# board.net
KiCad netlist of a schematic drawn in EAGLE
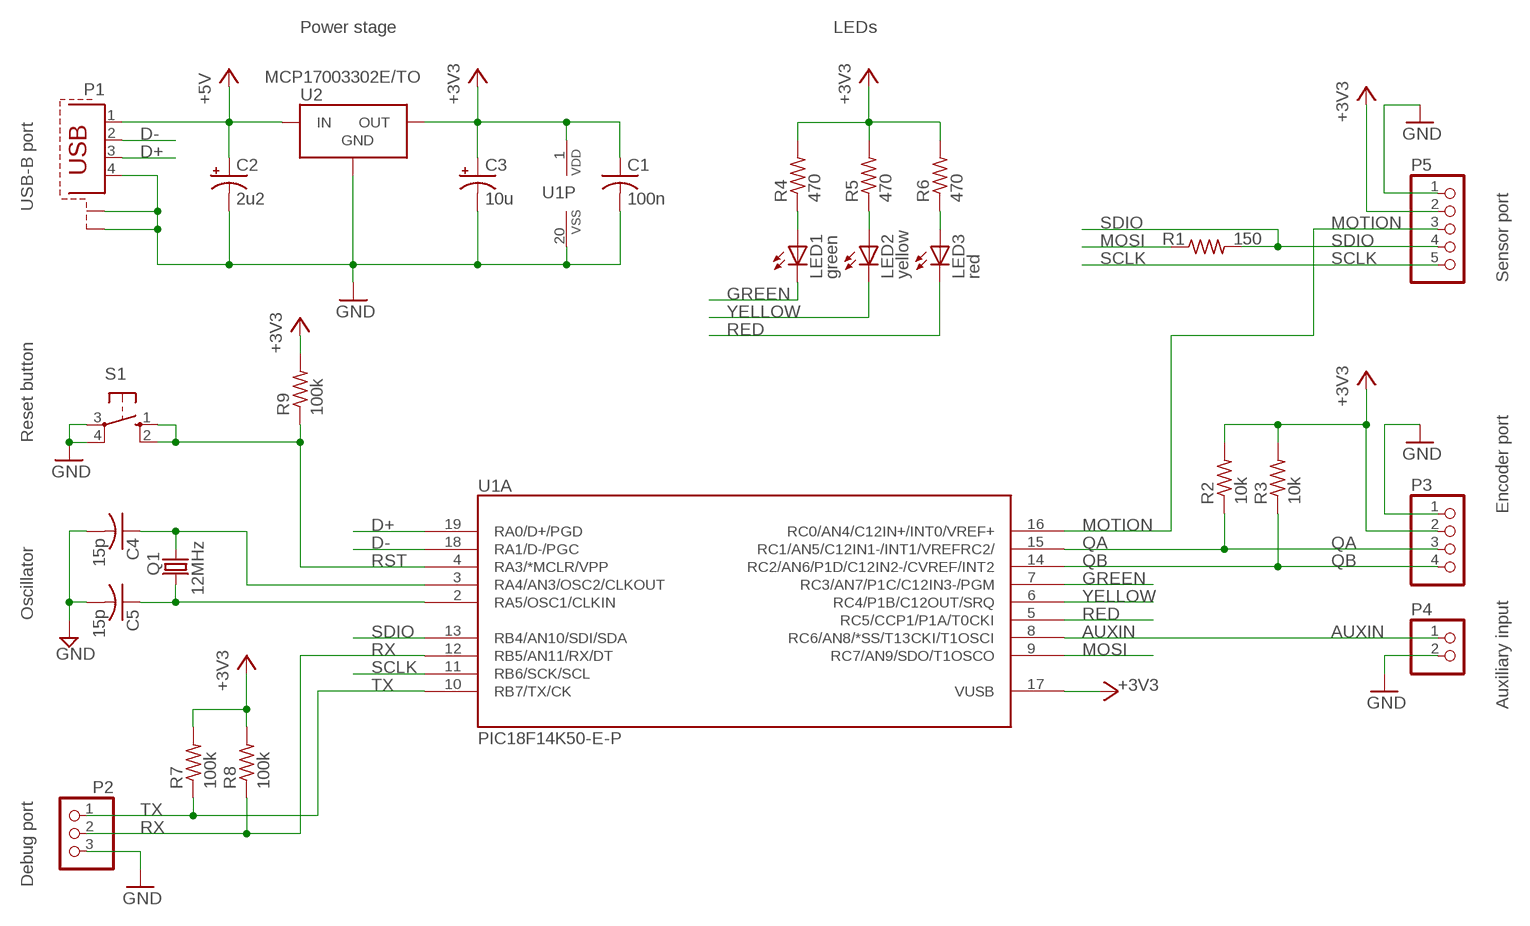
[diagram p0: schematic, sheet 1]

(export (version "E")
  (design (tool "Eeschema 10.0.6"))
  (components
    (comp (ref "C1")
      (value "100n")
      (footprint "eagle-import:C025-025X050")
      (libsource (lib "eagle-import") (part "C-US025-025X050"))
    )
    (comp (ref "C2")
      (value "2u2")
      (footprint "eagle-import:E2-5")
      (libsource (lib "eagle-import") (part "CPOL-USE2-5"))
    )
    (comp (ref "C3")
      (value "10u")
      (footprint "eagle-import:E2-5")
      (libsource (lib "eagle-import") (part "CPOL-USE2-5"))
    )
    (comp (ref "C4")
      (value "15p")
      (footprint "eagle-import:C025-025X050")
      (libsource (lib "eagle-import") (part "C-US025-025X050"))
    )
    (comp (ref "C5")
      (value "15p")
      (footprint "eagle-import:C025-025X050")
      (libsource (lib "eagle-import") (part "C-US025-025X050"))
    )
    (comp (ref "LED1")
      (value "green")
      (footprint "eagle-import:LED3MM")
      (libsource (lib "eagle-import") (part "LED3MM"))
    )
    (comp (ref "LED2")
      (value "yellow")
      (footprint "eagle-import:LED3MM")
      (libsource (lib "eagle-import") (part "LED3MM"))
    )
    (comp (ref "LED3")
      (value "red")
      (footprint "eagle-import:LED3MM")
      (libsource (lib "eagle-import") (part "LED3MM"))
    )
    (comp (ref "P1")
      (value "PN61729-S")
      (footprint "eagle-import:PN61729-S")
      (libsource (lib "eagle-import") (part "PN61729-S"))
    )
    (comp (ref "P2")
      (value "PINHD-1X3")
      (footprint "eagle-import:1X03")
      (libsource (lib "eagle-import") (part "PINHD-1X3"))
    )
    (comp (ref "P3")
      (value "PINHD-1X4")
      (footprint "eagle-import:1X04")
      (libsource (lib "eagle-import") (part "PINHD-1X4"))
    )
    (comp (ref "P4")
      (value "PINHD-1X2")
      (footprint "eagle-import:1X02")
      (libsource (lib "eagle-import") (part "PINHD-1X2"))
    )
    (comp (ref "P5")
      (value "PINHD-1X5")
      (footprint "eagle-import:1X05")
      (libsource (lib "eagle-import") (part "PINHD-1X5"))
    )
    (comp (ref "Q1")
      (value "12MHz")
      (footprint "eagle-import:HC49_S")
      (libsource (lib "eagle-import") (part "CRYSTALHC49S"))
    )
    (comp (ref "R1")
      (value "150")
      (footprint "eagle-import:0207_10")
      (libsource (lib "eagle-import") (part "R-US_0207/10"))
    )
    (comp (ref "R2")
      (value "10k")
      (footprint "eagle-import:0204_5")
      (libsource (lib "eagle-import") (part "R-US_0204/5"))
    )
    (comp (ref "R3")
      (value "10k")
      (footprint "eagle-import:0204_5")
      (libsource (lib "eagle-import") (part "R-US_0204/5"))
    )
    (comp (ref "R4")
      (value "470")
      (footprint "eagle-import:0204_5")
      (libsource (lib "eagle-import") (part "R-US_0204/5"))
    )
    (comp (ref "R5")
      (value "470")
      (footprint "eagle-import:0204_5")
      (libsource (lib "eagle-import") (part "R-US_0204/5"))
    )
    (comp (ref "R6")
      (value "470")
      (footprint "eagle-import:0204_5")
      (libsource (lib "eagle-import") (part "R-US_0204/5"))
    )
    (comp (ref "R7")
      (value "100k")
      (footprint "eagle-import:0204_5")
      (libsource (lib "eagle-import") (part "R-US_0204/5"))
    )
    (comp (ref "R8")
      (value "100k")
      (footprint "eagle-import:0204_5")
      (libsource (lib "eagle-import") (part "R-US_0204/5"))
    )
    (comp (ref "R9")
      (value "100k")
      (footprint "eagle-import:0204_5")
      (libsource (lib "eagle-import") (part "R-US_0204/5"))
    )
    (comp (ref "S1")
      (value "10-XX")
      (footprint "eagle-import:B3F-10XX")
      (fields (field (name "MPN") "B3F-1000"))
      (libsource (lib "eagle-import") (part "10-XX"))
    )
    (comp (ref "U1")
      (value "PIC18F14K50-E-P")
      (footprint "eagle-import:DIL20")
      (libsource (lib "eagle-import") (part "PIC18F14K50-E-P"))
    )
    (comp (ref "U2")
      (value "MCP17003302E/TO")
      (footprint "eagle-import:TO-92")
      (libsource (lib "eagle-import") (part "MCP17003302E/TO"))
    )
  )
  (nets
    (net (code "1") (name "+3V3") (class "Default")
      (node (ref "C1") (pin "1") (pinfunction "1_1") (pintype "passive"))
      (node (ref "C3") (pin "+") (pinfunction "+_+") (pintype "passive"))
      (node (ref "P3") (pin "2") (pinfunction "2_2") (pintype "passive"))
      (node (ref "P5") (pin "2") (pinfunction "2_2") (pintype "passive"))
      (node (ref "R2") (pin "2") (pinfunction "2_2") (pintype "passive"))
      (node (ref "R3") (pin "2") (pinfunction "2_2") (pintype "passive"))
      (node (ref "R4") (pin "2") (pinfunction "2_2") (pintype "passive"))
      (node (ref "R5") (pin "2") (pinfunction "2_2") (pintype "passive"))
      (node (ref "R6") (pin "2") (pinfunction "2_2") (pintype "passive"))
      (node (ref "R7") (pin "2") (pinfunction "2_2") (pintype "passive"))
      (node (ref "R8") (pin "2") (pinfunction "2_2") (pintype "passive"))
      (node (ref "R9") (pin "2") (pinfunction "2_2") (pintype "passive"))
      (node (ref "U1") (pin "1") (pinfunction "VDD_1") (pintype "passive"))
      (node (ref "U1") (pin "17") (pinfunction "VUSB_17") (pintype "passive"))
      (node (ref "U2") (pin "OUT") (pinfunction "OUT_OUT") (pintype "passive"))
    )
    (net (code "2") (name "+5V") (class "Default")
      (node (ref "C2") (pin "+") (pinfunction "+_+") (pintype "passive"))
      (node (ref "P1") (pin "1") (pinfunction "1_1") (pintype "passive"))
      (node (ref "U2") (pin "IN") (pinfunction "IN_IN") (pintype "passive"))
    )
    (net (code "3") (name "/AUXIN") (class "Default")
      (node (ref "P4") (pin "1") (pinfunction "1_1") (pintype "passive"))
      (node (ref "U1") (pin "8") (pinfunction "RC6/AN8/*SS/T13CKI/T1OSCI_8") (pintype "bidirectional"))
    )
    (net (code "4") (name "/D+") (class "Default")
      (node (ref "P1") (pin "3") (pinfunction "3_3") (pintype "passive"))
      (node (ref "U1") (pin "19") (pinfunction "RA0/D+/PGD_19") (pintype "bidirectional"))
    )
    (net (code "5") (name "/D-") (class "Default")
      (node (ref "P1") (pin "2") (pinfunction "2_2") (pintype "passive"))
      (node (ref "U1") (pin "18") (pinfunction "RA1/D-/PGC_18") (pintype "bidirectional"))
    )
    (net (code "6") (name "/GREEN") (class "Default")
      (node (ref "LED1") (pin "K") (pinfunction "C_K") (pintype "passive"))
      (node (ref "U1") (pin "7") (pinfunction "RC3/AN7/P1C/C12IN3-/PGM_7") (pintype "bidirectional"))
    )
    (net (code "7") (name "/MOSI") (class "Default")
      (node (ref "R1") (pin "1") (pinfunction "1_1") (pintype "passive"))
      (node (ref "U1") (pin "9") (pinfunction "RC7/AN9/SDO/T1OSCO_9") (pintype "bidirectional"))
    )
    (net (code "8") (name "/MOTION") (class "Default")
      (node (ref "P5") (pin "3") (pinfunction "3_3") (pintype "passive"))
      (node (ref "U1") (pin "16") (pinfunction "RC0/AN4/C12IN+/INT0/VREF+_16") (pintype "bidirectional"))
    )
    (net (code "9") (name "/QA") (class "Default")
      (node (ref "P3") (pin "3") (pinfunction "3_3") (pintype "passive"))
      (node (ref "R2") (pin "1") (pinfunction "1_1") (pintype "passive"))
      (node (ref "U1") (pin "15") (pinfunction "RC1/AN5/C12IN1-/INT1/VREFRC2/_15") (pintype "bidirectional"))
    )
    (net (code "10") (name "/QB") (class "Default")
      (node (ref "P3") (pin "4") (pinfunction "4_4") (pintype "passive"))
      (node (ref "R3") (pin "1") (pinfunction "1_1") (pintype "passive"))
      (node (ref "U1") (pin "14") (pinfunction "RC2/AN6/P1D/C12IN2-/CVREF/INT2_14") (pintype "bidirectional"))
    )
    (net (code "11") (name "/RED") (class "Default")
      (node (ref "LED3") (pin "K") (pinfunction "C_K") (pintype "passive"))
      (node (ref "U1") (pin "5") (pinfunction "RC5/CCP1/P1A/T0CKI_5") (pintype "bidirectional"))
    )
    (net (code "12") (name "/RST") (class "Default")
      (node (ref "R9") (pin "1") (pinfunction "1_1") (pintype "passive"))
      (node (ref "S1") (pin "1") (pinfunction "S_1") (pintype "passive"))
      (node (ref "S1") (pin "2") (pinfunction "S1_2") (pintype "passive"))
      (node (ref "U1") (pin "4") (pinfunction "RA3/*MCLR/VPP_4") (pintype "input"))
    )
    (net (code "13") (name "/RX") (class "Default")
      (node (ref "P2") (pin "2") (pinfunction "2_2") (pintype "passive"))
      (node (ref "R8") (pin "1") (pinfunction "1_1") (pintype "passive"))
      (node (ref "U1") (pin "12") (pinfunction "RB5/AN11/RX/DT_12") (pintype "bidirectional"))
    )
    (net (code "14") (name "/SCLK") (class "Default")
      (node (ref "P5") (pin "5") (pinfunction "5_5") (pintype "passive"))
      (node (ref "U1") (pin "11") (pinfunction "RB6/SCK/SCL_11") (pintype "bidirectional"))
    )
    (net (code "15") (name "/SDIO") (class "Default")
      (node (ref "P5") (pin "4") (pinfunction "4_4") (pintype "passive"))
      (node (ref "R1") (pin "2") (pinfunction "2_2") (pintype "passive"))
      (node (ref "U1") (pin "13") (pinfunction "RB4/AN10/SDI/SDA_13") (pintype "bidirectional"))
    )
    (net (code "16") (name "/TX") (class "Default")
      (node (ref "P2") (pin "1") (pinfunction "1_1") (pintype "passive"))
      (node (ref "R7") (pin "1") (pinfunction "1_1") (pintype "passive"))
      (node (ref "U1") (pin "10") (pinfunction "RB7/TX/CK_10") (pintype "bidirectional"))
    )
    (net (code "17") (name "/YELLOW") (class "Default")
      (node (ref "LED2") (pin "K") (pinfunction "C_K") (pintype "passive"))
      (node (ref "U1") (pin "6") (pinfunction "RC4/P1B/C12OUT/SRQ_6") (pintype "bidirectional"))
    )
    (net (code "18") (name "GND") (class "Default")
      (node (ref "C1") (pin "2") (pinfunction "2_2") (pintype "passive"))
      (node (ref "C2") (pin "-") (pinfunction "-_-") (pintype "passive"))
      (node (ref "C3") (pin "-") (pinfunction "-_-") (pintype "passive"))
      (node (ref "C4") (pin "2") (pinfunction "2_2") (pintype "passive"))
      (node (ref "C5") (pin "2") (pinfunction "2_2") (pintype "passive"))
      (node (ref "P1") (pin "4") (pinfunction "4_4") (pintype "passive"))
      (node (ref "P1") (pin "S1") (pinfunction "S1_S1") (pintype "passive"))
      (node (ref "P1") (pin "S2") (pinfunction "S2_S2") (pintype "passive"))
      (node (ref "P2") (pin "3") (pinfunction "3_3") (pintype "passive"))
      (node (ref "P3") (pin "1") (pinfunction "1_1") (pintype "passive"))
      (node (ref "P4") (pin "2") (pinfunction "2_2") (pintype "passive"))
      (node (ref "P5") (pin "1") (pinfunction "1_1") (pintype "passive"))
      (node (ref "S1") (pin "3") (pinfunction "P_3") (pintype "passive"))
      (node (ref "S1") (pin "4") (pinfunction "P1_4") (pintype "passive"))
      (node (ref "U1") (pin "20") (pinfunction "VSS_20") (pintype "passive"))
      (node (ref "U2") (pin "GND") (pinfunction "GND_GND") (pintype "passive"))
    )
    (net (code "19") (name "Net-(LED1-PadA)") (class "Default")
      (node (ref "LED1") (pin "A") (pinfunction "A_A") (pintype "passive"))
      (node (ref "R4") (pin "1") (pinfunction "1_1") (pintype "passive"))
    )
    (net (code "20") (name "Net-(LED2-PadA)") (class "Default")
      (node (ref "LED2") (pin "A") (pinfunction "A_A") (pintype "passive"))
      (node (ref "R5") (pin "1") (pinfunction "1_1") (pintype "passive"))
    )
    (net (code "21") (name "Net-(LED3-PadA)") (class "Default")
      (node (ref "LED3") (pin "A") (pinfunction "A_A") (pintype "passive"))
      (node (ref "R6") (pin "1") (pinfunction "1_1") (pintype "passive"))
    )
    (net (code "22") (name "Net-(U1A-RA4{slash}AN3{slash}OSC2{slash}CLKOUT)") (class "Default")
      (node (ref "C4") (pin "1") (pinfunction "1_1") (pintype "passive"))
      (node (ref "Q1") (pin "1") (pinfunction "1_1") (pintype "passive"))
      (node (ref "U1") (pin "3") (pinfunction "RA4/AN3/OSC2/CLKOUT_3") (pintype "bidirectional"))
    )
    (net (code "23") (name "Net-(U1A-RA5{slash}OSC1{slash}CLKIN)") (class "Default")
      (node (ref "C5") (pin "1") (pinfunction "1_1") (pintype "passive"))
      (node (ref "Q1") (pin "2") (pinfunction "2_2") (pintype "passive"))
      (node (ref "U1") (pin "2") (pinfunction "RA5/OSC1/CLKIN_2") (pintype "bidirectional"))
    )
  )
)
